# SCH_Beekeeper_2024-03-11.net
KiCad netlist of a schematic drawn in EasyEDA
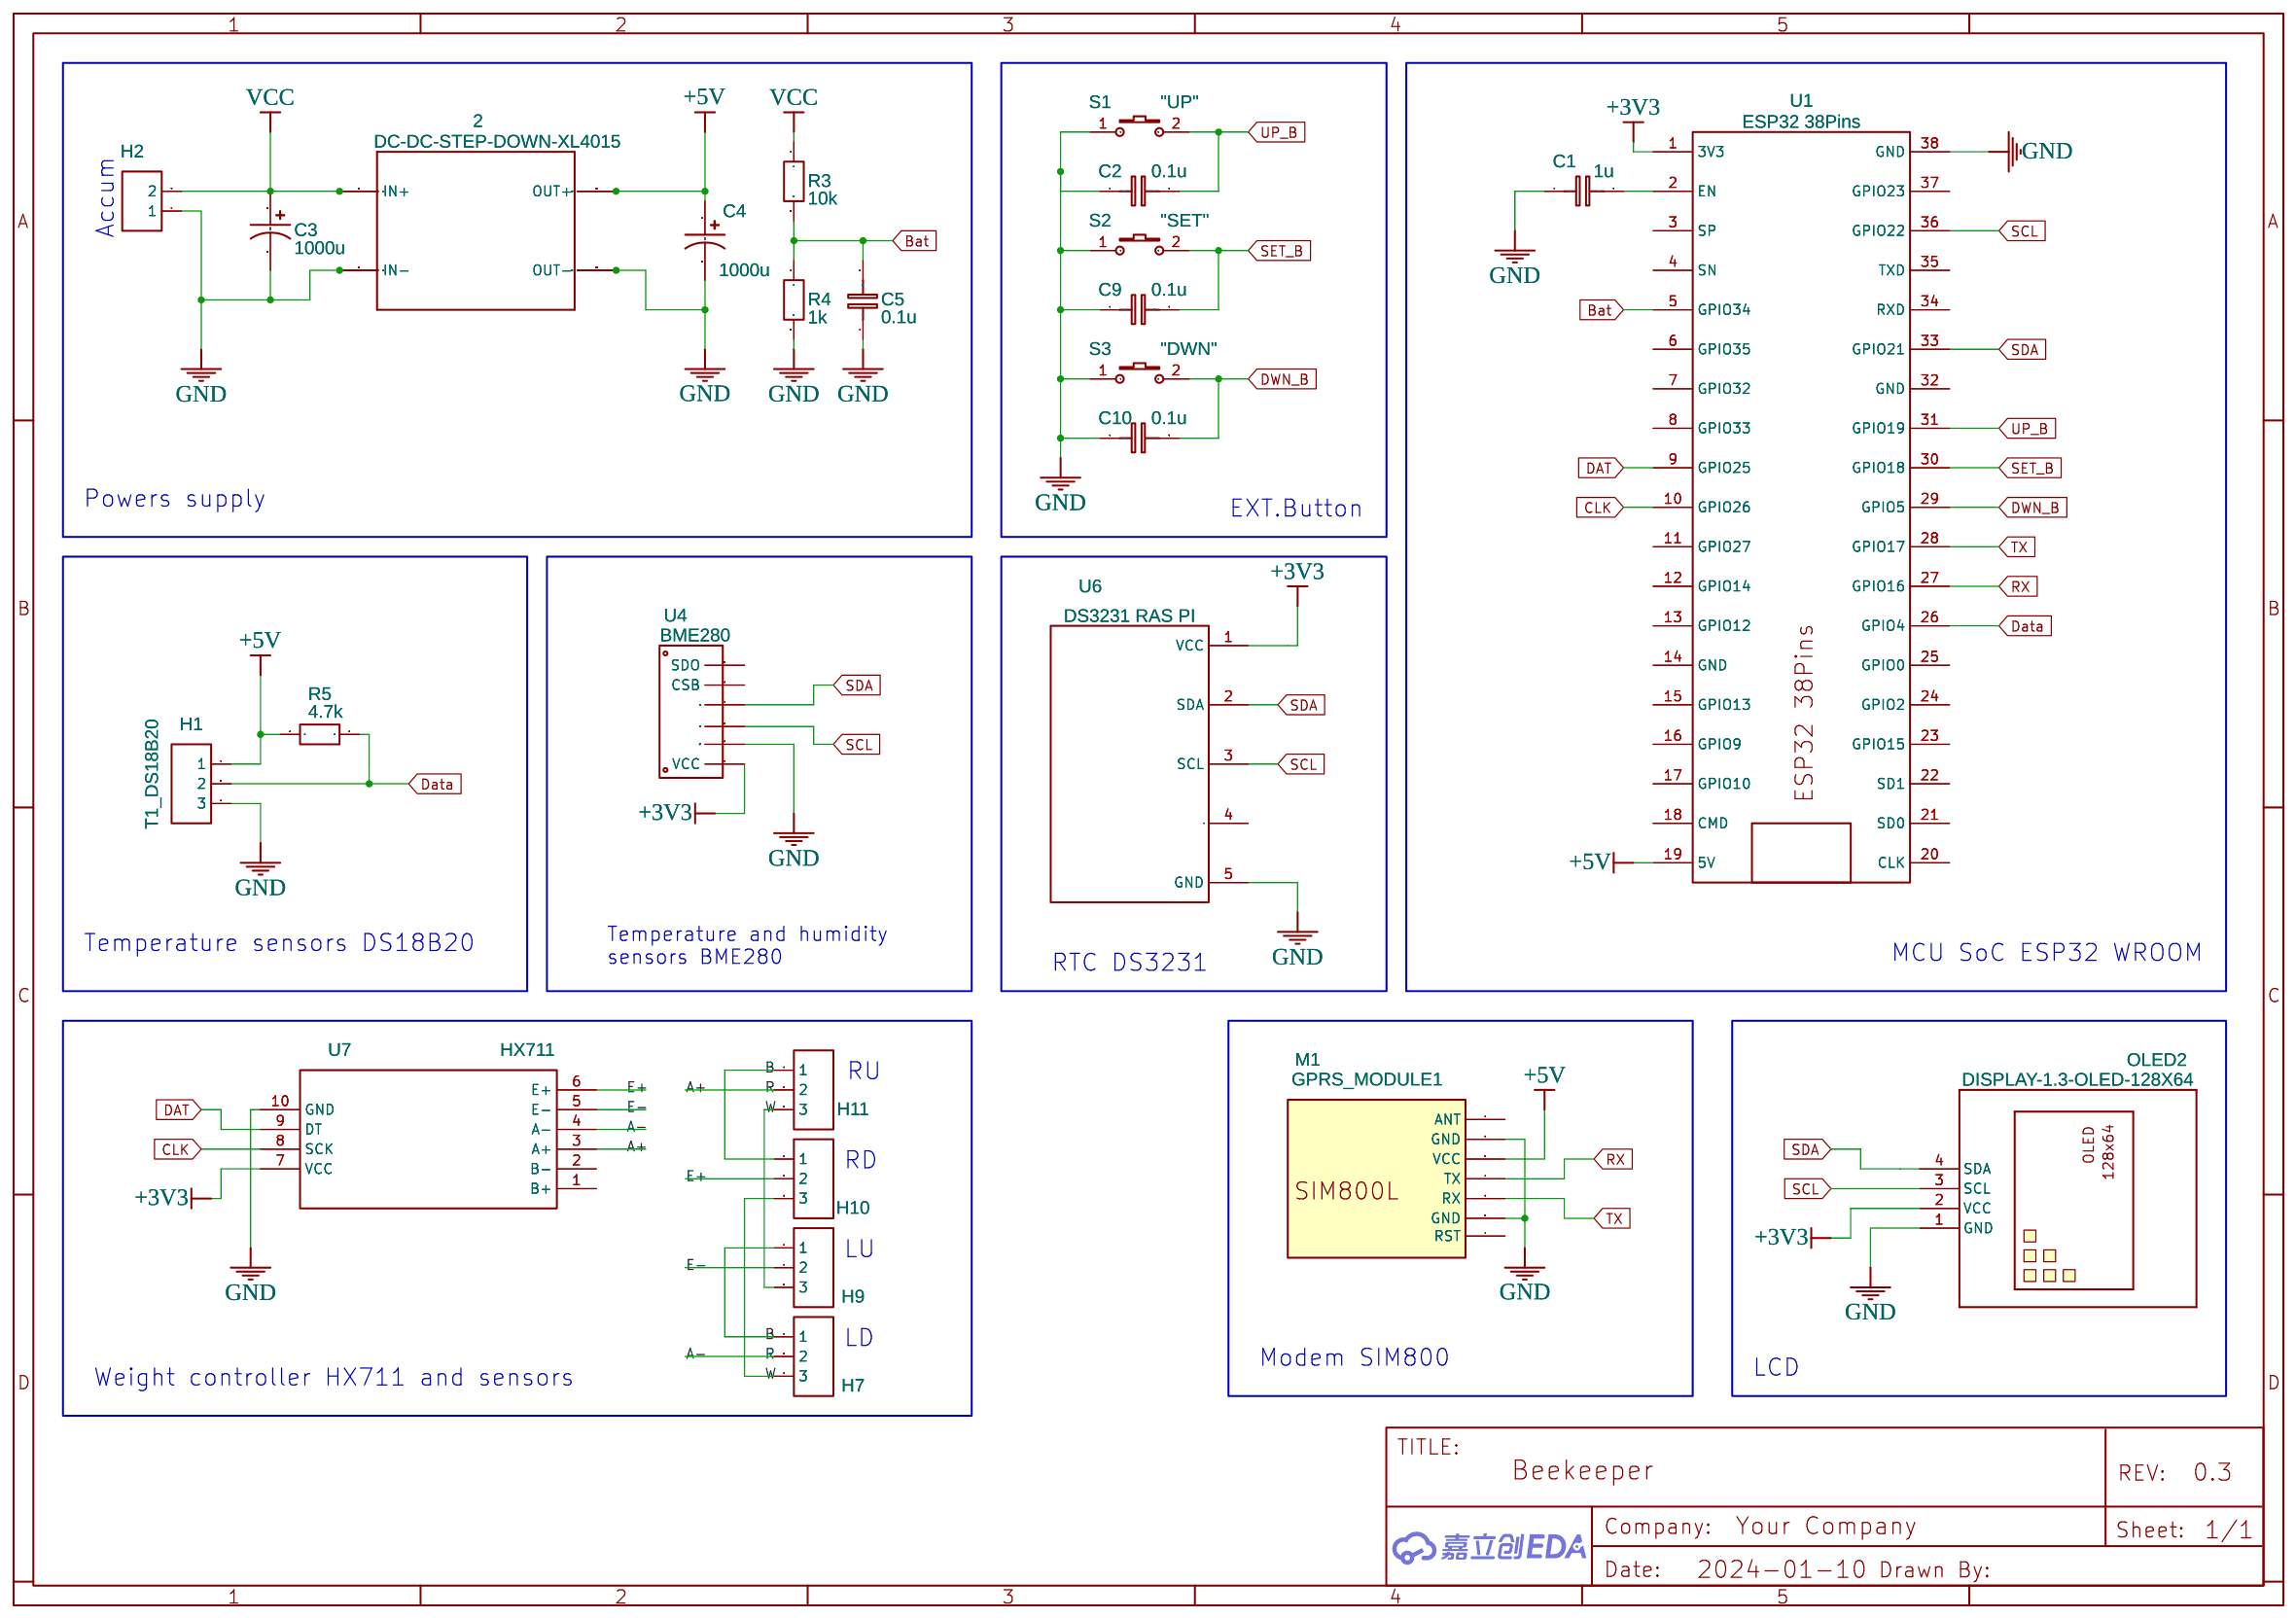
[diagram p0: schematic sheet]

(export (version "E")
  (design (tool "Eeschema 10.0.6"))
  (components
    (comp (ref "2") (value "DC-DC-STEP-DOWN-XL4015") (libsource (lib "") (part "DC-DC-STEP-DOWN-XL4015")))
    (comp (ref "C1") (value "1u") (libsource (lib "") (part "C_0805_EU")))
    (comp (ref "C2") (value "0.1u") (libsource (lib "") (part "C_0805_EU")))
    (comp (ref "C3") (value "1000u") (libsource (lib "") (part "CE_TH_D12.5×F5.0_US_1")))
    (comp (ref "C4") (value "1000u") (libsource (lib "") (part "CE_TH_D12.5×F5.0_US")))
    (comp (ref "C5") (value "0.1u") (libsource (lib "") (part "C_0805_EU_1")))
    (comp (ref "C9") (value "0.1u") (libsource (lib "") (part "C_0805_EU")))
    (comp (ref "C10") (value "0.1u") (libsource (lib "") (part "C_0805_EU")))
    (comp (ref "H1") (value "T1_DS18B20") (libsource (lib "") (part "HDR-F-2.54_1x3_1")))
    (comp (ref "H2") (value "HDR-F-2.54_1x2") (libsource (lib "") (part "HDR-F-2.54_1x2")))
    (comp (ref "H7") (value "HDR-F-2.54_1x3") (libsource (lib "") (part "HDR-F-2.54_1x3")))
    (comp (ref "H9") (value "HDR-F-2.54_1x3") (libsource (lib "") (part "HDR-F-2.54_1x3")))
    (comp (ref "H10") (value "HDR-F-2.54_1x3") (libsource (lib "") (part "HDR-F-2.54_1x3")))
    (comp (ref "H11") (value "HDR-F-2.54_1x3") (libsource (lib "") (part "HDR-F-2.54_1x3")))
    (comp (ref "M1")
      (value "GPRS_MODULE1")
      (fields (field (name "Manufacturer Part") "SIM800L") (field (name "Manufacturer") "SIMCOM"))
      (libsource (lib "") (part "GPRS_MODULE1"))
    )
    (comp (ref "OLED2")
      (value "DISPLAY-1.3-OLED-128X64")
      (libsource (lib "") (part "DISPLAY-1.3-OLED-128X64-I2C"))
    )
    (comp (ref "R3") (value "10k") (libsource (lib "") (part "R_1206_EU")))
    (comp (ref "R4") (value "1k") (libsource (lib "") (part "R_1206_EU")))
    (comp (ref "R5") (value "4.7k") (libsource (lib "") (part "R_1206_EU_1")))
    (comp (ref "S1")
      (value "\"UP\"")
      (fields (field (name "Manufacturer Part") "K2-1107ST-A4SW-06"))
      (libsource (lib "") (part "K2-3.6×6.1_SMD"))
    )
    (comp (ref "S2")
      (value "\"SET\"")
      (fields (field (name "Manufacturer Part") "K2-1107ST-A4SW-06"))
      (libsource (lib "") (part "K2-3.6×6.1_SMD"))
    )
    (comp (ref "S3")
      (value "\"DWN\"")
      (fields (field (name "Manufacturer Part") "K2-1107ST-A4SW-06"))
      (libsource (lib "") (part "K2-3.6×6.1_SMD"))
    )
    (comp (ref "U1") (value "ESP32 38Pins") (libsource (lib "") (part "ESP32 38Pins")))
    (comp (ref "U4") (value "BME280") (libsource (lib "") (part "BME280")))
    (comp (ref "U6")
      (value "DS3231 RAS PI")
      (fields (field (name "Manufacturer Part") "New SchematicLib"))
      (libsource (lib "") (part "DS3231 RAS PI"))
    )
    (comp (ref "U7") (value "HX711") (libsource (lib "") (part "HX711")))
  )
  (nets
    (net (code "1") (name "+3V3") (class "Default")
      (node (ref "OLED2") (pin "2") (pinfunction "VCC_2") (pintype "bidirectional"))
      (node (ref "U1") (pin "1") (pinfunction "3V3_1") (pintype "unspecified"))
      (node (ref "U4") (pin "1") (pinfunction "VCC_1") (pintype "unspecified"))
      (node (ref "U6") (pin "1") (pinfunction "VCC_1") (pintype "unspecified"))
      (node (ref "U7") (pin "7") (pinfunction "VCC_7") (pintype "unspecified"))
    )
    (net (code "2") (name "+5V") (class "Default")
      (node (ref "2") (pin "O+") (pinfunction "OUT+_O+") (pintype "bidirectional"))
      (node (ref "2") (pin "OUT+") (pinfunction "OUT+_OUT+") (pintype "bidirectional"))
      (node (ref "C4") (pin "1") (pinfunction "1_1") (pintype "unspecified"))
      (node (ref "H1") (pin "1") (pinfunction "1_1") (pintype "input"))
      (node (ref "M1") (pin "3") (pinfunction "VCC_3") (pintype "input"))
      (node (ref "R5") (pin "2") (pinfunction "2_2") (pintype "unspecified"))
      (node (ref "U1") (pin "19") (pinfunction "5V_19") (pintype "unspecified"))
    )
    (net (code "3") (name "/A+") (class "Default")
      (node (ref "H11") (pin "2") (pinfunction "2_2") (pintype "input"))
      (node (ref "H7") (pin "2") (pinfunction "2_2") (pintype "input"))
      (node (ref "U7") (pin "3") (pinfunction "A+_3") (pintype "unspecified"))
      (node (ref "U7") (pin "4") (pinfunction "A-_4") (pintype "unspecified"))
    )
    (net (code "4") (name "/B") (class "Default")
      (node (ref "H10") (pin "1") (pinfunction "1_1") (pintype "input"))
      (node (ref "H11") (pin "1") (pinfunction "1_1") (pintype "input"))
      (node (ref "H7") (pin "1") (pinfunction "1_1") (pintype "input"))
      (node (ref "H9") (pin "1") (pinfunction "1_1") (pintype "input"))
    )
    (net (code "5") (name "/E+") (class "Default")
      (node (ref "H10") (pin "2") (pinfunction "2_2") (pintype "input"))
      (node (ref "U7") (pin "6") (pinfunction "E+_6") (pintype "unspecified"))
    )
    (net (code "6") (name "/E-") (class "Default")
      (node (ref "H9") (pin "2") (pinfunction "2_2") (pintype "input"))
      (node (ref "U7") (pin "5") (pinfunction "E-_5") (pintype "unspecified"))
    )
    (net (code "7") (name "/W") (class "Default")
      (node (ref "H10") (pin "3") (pinfunction "3_3") (pintype "input"))
      (node (ref "H11") (pin "3") (pinfunction "3_3") (pintype "input"))
      (node (ref "H7") (pin "3") (pinfunction "3_3") (pintype "input"))
      (node (ref "H9") (pin "3") (pinfunction "3_3") (pintype "input"))
    )
    (net (code "8") (name "Bat") (class "Default")
      (node (ref "C5") (pin "2") (pinfunction "2_2") (pintype "unspecified"))
      (node (ref "R3") (pin "2") (pinfunction "2_2") (pintype "unspecified"))
      (node (ref "R4") (pin "1") (pinfunction "1_1") (pintype "unspecified"))
      (node (ref "U1") (pin "5") (pinfunction "GPIO34_5") (pintype "unspecified"))
    )
    (net (code "9") (name "CLK") (class "Default")
      (node (ref "U1") (pin "10") (pinfunction "GPIO26_10") (pintype "unspecified"))
      (node (ref "U7") (pin "8") (pinfunction "SCK_8") (pintype "unspecified"))
    )
    (net (code "10") (name "DAT") (class "Default")
      (node (ref "U1") (pin "9") (pinfunction "GPIO25_9") (pintype "unspecified"))
      (node (ref "U7") (pin "9") (pinfunction "DT_9") (pintype "unspecified"))
    )
    (net (code "11") (name "DWN_B") (class "Default")
      (node (ref "C10") (pin "2") (pinfunction "2_2") (pintype "unspecified"))
      (node (ref "S3") (pin "2") (pinfunction "2_2") (pintype "unspecified"))
      (node (ref "U1") (pin "29") (pinfunction "GPIO5_29") (pintype "unspecified"))
    )
    (net (code "12") (name "Data") (class "Default")
      (node (ref "H1") (pin "2") (pinfunction "2_2") (pintype "input"))
      (node (ref "R5") (pin "1") (pinfunction "1_1") (pintype "unspecified"))
      (node (ref "U1") (pin "26") (pinfunction "GPIO4_26") (pintype "unspecified"))
    )
    (net (code "13") (name "GND") (class "Default")
      (node (ref "2") (pin "I-") (pinfunction "IN-_I-") (pintype "bidirectional"))
      (node (ref "2") (pin "IN-") (pinfunction "IN-_IN-") (pintype "bidirectional"))
      (node (ref "2") (pin "O-") (pinfunction "OUT-_O-") (pintype "bidirectional"))
      (node (ref "2") (pin "OUT-") (pinfunction "OUT-_OUT-") (pintype "bidirectional"))
      (node (ref "C1") (pin "1") (pinfunction "1_1") (pintype "unspecified"))
      (node (ref "C10") (pin "1") (pinfunction "1_1") (pintype "unspecified"))
      (node (ref "C2") (pin "1") (pinfunction "1_1") (pintype "unspecified"))
      (node (ref "C3") (pin "2") (pinfunction "2_2") (pintype "unspecified"))
      (node (ref "C4") (pin "2") (pinfunction "2_2") (pintype "unspecified"))
      (node (ref "C5") (pin "1") (pinfunction "1_1") (pintype "unspecified"))
      (node (ref "C9") (pin "1") (pinfunction "1_1") (pintype "unspecified"))
      (node (ref "H1") (pin "3") (pinfunction "3_3") (pintype "input"))
      (node (ref "H2") (pin "1") (pinfunction "1_1") (pintype "input"))
      (node (ref "M1") (pin "2") (pinfunction "GND_2") (pintype "input"))
      (node (ref "M1") (pin "6") (pinfunction "GND_6") (pintype "input"))
      (node (ref "OLED2") (pin "1") (pinfunction "GND_1") (pintype "bidirectional"))
      (node (ref "R4") (pin "2") (pinfunction "2_2") (pintype "unspecified"))
      (node (ref "S1") (pin "1") (pinfunction "1_1") (pintype "unspecified"))
      (node (ref "S2") (pin "1") (pinfunction "1_1") (pintype "unspecified"))
      (node (ref "S3") (pin "1") (pinfunction "1_1") (pintype "unspecified"))
      (node (ref "U1") (pin "38") (pinfunction "GND_38") (pintype "unspecified"))
      (node (ref "U4") (pin "2") (pinfunction "GND_2") (pintype "unspecified"))
      (node (ref "U6") (pin "5") (pinfunction "GND_5") (pintype "unspecified"))
      (node (ref "U7") (pin "10") (pinfunction "GND_10") (pintype "unspecified"))
    )
    (net (code "14") (name "Net-(U1-EN)") (class "Default")
      (node (ref "C1") (pin "2") (pinfunction "2_2") (pintype "unspecified"))
      (node (ref "U1") (pin "2") (pinfunction "EN_2") (pintype "unspecified"))
    )
    (net (code "15") (name "RX") (class "Default")
      (node (ref "M1") (pin "4") (pinfunction "TX_4") (pintype "input"))
      (node (ref "U1") (pin "27") (pinfunction "GPIO16_27") (pintype "unspecified"))
    )
    (net (code "16") (name "SCL") (class "Default")
      (node (ref "OLED2") (pin "3") (pinfunction "SCL_3") (pintype "bidirectional"))
      (node (ref "U1") (pin "36") (pinfunction "GPIO22_36") (pintype "unspecified"))
      (node (ref "U4") (pin "3") (pinfunction "SCL_3") (pintype "unspecified"))
      (node (ref "U6") (pin "3") (pinfunction "SCL_3") (pintype "unspecified"))
    )
    (net (code "17") (name "SDA") (class "Default")
      (node (ref "OLED2") (pin "4") (pinfunction "SDA_4") (pintype "bidirectional"))
      (node (ref "U1") (pin "33") (pinfunction "GPIO21_33") (pintype "unspecified"))
      (node (ref "U4") (pin "4") (pinfunction "SDA_4") (pintype "unspecified"))
      (node (ref "U6") (pin "2") (pinfunction "SDA_2") (pintype "unspecified"))
    )
    (net (code "18") (name "SET_B") (class "Default")
      (node (ref "C9") (pin "2") (pinfunction "2_2") (pintype "unspecified"))
      (node (ref "S2") (pin "2") (pinfunction "2_2") (pintype "unspecified"))
      (node (ref "U1") (pin "30") (pinfunction "GPIO18_30") (pintype "unspecified"))
    )
    (net (code "19") (name "TX") (class "Default")
      (node (ref "M1") (pin "5") (pinfunction "RX_5") (pintype "input"))
      (node (ref "U1") (pin "28") (pinfunction "GPIO17_28") (pintype "unspecified"))
    )
    (net (code "20") (name "UP_B") (class "Default")
      (node (ref "C2") (pin "2") (pinfunction "2_2") (pintype "unspecified"))
      (node (ref "S1") (pin "2") (pinfunction "2_2") (pintype "unspecified"))
      (node (ref "U1") (pin "31") (pinfunction "GPIO19_31") (pintype "unspecified"))
    )
    (net (code "21") (name "VCC") (class "Default")
      (node (ref "2") (pin "I+") (pinfunction "IN+_I+") (pintype "bidirectional"))
      (node (ref "2") (pin "IN+") (pinfunction "IN+_IN+") (pintype "bidirectional"))
      (node (ref "C3") (pin "1") (pinfunction "1_1") (pintype "unspecified"))
      (node (ref "H2") (pin "2") (pinfunction "2_2") (pintype "input"))
      (node (ref "R3") (pin "1") (pinfunction "1_1") (pintype "unspecified"))
    )
    (net (code "22") (name "unconnected-(M1-ANT-Pad1)") (class "Default")
      (node (ref "M1") (pin "1") (pinfunction "ANT_1") (pintype "input"))
    )
    (net (code "23") (name "unconnected-(M1-RST-Pad7)") (class "Default")
      (node (ref "M1") (pin "7") (pinfunction "RST_7") (pintype "input"))
    )
    (net (code "24") (name "unconnected-(U1-CLK-Pad20)") (class "Default")
      (node (ref "U1") (pin "20") (pinfunction "CLK_20") (pintype "unspecified"))
    )
    (net (code "25") (name "unconnected-(U1-CMD-Pad18)") (class "Default")
      (node (ref "U1") (pin "18") (pinfunction "CMD_18") (pintype "unspecified"))
    )
    (net (code "26") (name "unconnected-(U1-GND-Pad14)") (class "Default")
      (node (ref "U1") (pin "14") (pinfunction "GND_14") (pintype "unspecified"))
    )
    (net (code "27") (name "unconnected-(U1-GND-Pad32)") (class "Default")
      (node (ref "U1") (pin "32") (pinfunction "GND_32") (pintype "unspecified"))
    )
    (net (code "28") (name "unconnected-(U1-GPIO0-Pad25)") (class "Default")
      (node (ref "U1") (pin "25") (pinfunction "GPIO0_25") (pintype "unspecified"))
    )
    (net (code "29") (name "unconnected-(U1-GPIO2-Pad24)") (class "Default")
      (node (ref "U1") (pin "24") (pinfunction "GPIO2_24") (pintype "unspecified"))
    )
    (net (code "30") (name "unconnected-(U1-GPIO9-Pad16)") (class "Default")
      (node (ref "U1") (pin "16") (pinfunction "GPIO9_16") (pintype "unspecified"))
    )
    (net (code "31") (name "unconnected-(U1-GPIO10-Pad17)") (class "Default")
      (node (ref "U1") (pin "17") (pinfunction "GPIO10_17") (pintype "unspecified"))
    )
    (net (code "32") (name "unconnected-(U1-GPIO12-Pad13)") (class "Default")
      (node (ref "U1") (pin "13") (pinfunction "GPIO12_13") (pintype "unspecified"))
    )
    (net (code "33") (name "unconnected-(U1-GPIO13-Pad15)") (class "Default")
      (node (ref "U1") (pin "15") (pinfunction "GPIO13_15") (pintype "unspecified"))
    )
    (net (code "34") (name "unconnected-(U1-GPIO14-Pad12)") (class "Default")
      (node (ref "U1") (pin "12") (pinfunction "GPIO14_12") (pintype "unspecified"))
    )
    (net (code "35") (name "unconnected-(U1-GPIO15-Pad23)") (class "Default")
      (node (ref "U1") (pin "23") (pinfunction "GPIO15_23") (pintype "unspecified"))
    )
    (net (code "36") (name "unconnected-(U1-GPIO23-Pad37)") (class "Default")
      (node (ref "U1") (pin "37") (pinfunction "GPIO23_37") (pintype "unspecified"))
    )
    (net (code "37") (name "unconnected-(U1-GPIO27-Pad11)") (class "Default")
      (node (ref "U1") (pin "11") (pinfunction "GPIO27_11") (pintype "unspecified"))
    )
    (net (code "38") (name "unconnected-(U1-GPIO32-Pad7)") (class "Default")
      (node (ref "U1") (pin "7") (pinfunction "GPIO32_7") (pintype "unspecified"))
    )
    (net (code "39") (name "unconnected-(U1-GPIO33-Pad8)") (class "Default")
      (node (ref "U1") (pin "8") (pinfunction "GPIO33_8") (pintype "unspecified"))
    )
    (net (code "40") (name "unconnected-(U1-GPIO35-Pad6)") (class "Default")
      (node (ref "U1") (pin "6") (pinfunction "GPIO35_6") (pintype "unspecified"))
    )
    (net (code "41") (name "unconnected-(U1-RXD-Pad34)") (class "Default")
      (node (ref "U1") (pin "34") (pinfunction "RXD_34") (pintype "unspecified"))
    )
    (net (code "42") (name "unconnected-(U1-SD0-Pad21)") (class "Default")
      (node (ref "U1") (pin "21") (pinfunction "SD0_21") (pintype "unspecified"))
    )
    (net (code "43") (name "unconnected-(U1-SD1-Pad22)") (class "Default")
      (node (ref "U1") (pin "22") (pinfunction "SD1_22") (pintype "unspecified"))
    )
    (net (code "44") (name "unconnected-(U1-SN-Pad4)") (class "Default")
      (node (ref "U1") (pin "4") (pinfunction "SN_4") (pintype "unspecified"))
    )
    (net (code "45") (name "unconnected-(U1-SP-Pad3)") (class "Default")
      (node (ref "U1") (pin "3") (pinfunction "SP_3") (pintype "unspecified"))
    )
    (net (code "46") (name "unconnected-(U1-TXD-Pad35)") (class "Default")
      (node (ref "U1") (pin "35") (pinfunction "TXD_35") (pintype "unspecified"))
    )
    (net (code "47") (name "unconnected-(U4-CSB-Pad5)") (class "Default")
      (node (ref "U4") (pin "5") (pinfunction "CSB_5") (pintype "unspecified"))
    )
    (net (code "48") (name "unconnected-(U4-SDO-Pad6)") (class "Default")
      (node (ref "U4") (pin "6") (pinfunction "SDO_6") (pintype "unspecified"))
    )
    (net (code "49") (name "unconnected-(U6-Pad4)") (class "Default")
      (node (ref "U6") (pin "4") (pinfunction "4_4") (pintype "unspecified"))
    )
    (net (code "50") (name "unconnected-(U7-B+-Pad1)") (class "Default")
      (node (ref "U7") (pin "1") (pinfunction "B+_1") (pintype "unspecified"))
    )
    (net (code "51") (name "unconnected-(U7-B--Pad2)") (class "Default")
      (node (ref "U7") (pin "2") (pinfunction "B-_2") (pintype "unspecified"))
    )
  )
)
